# ledHeart.net
KiCad netlist of a schematic drawn in EAGLE
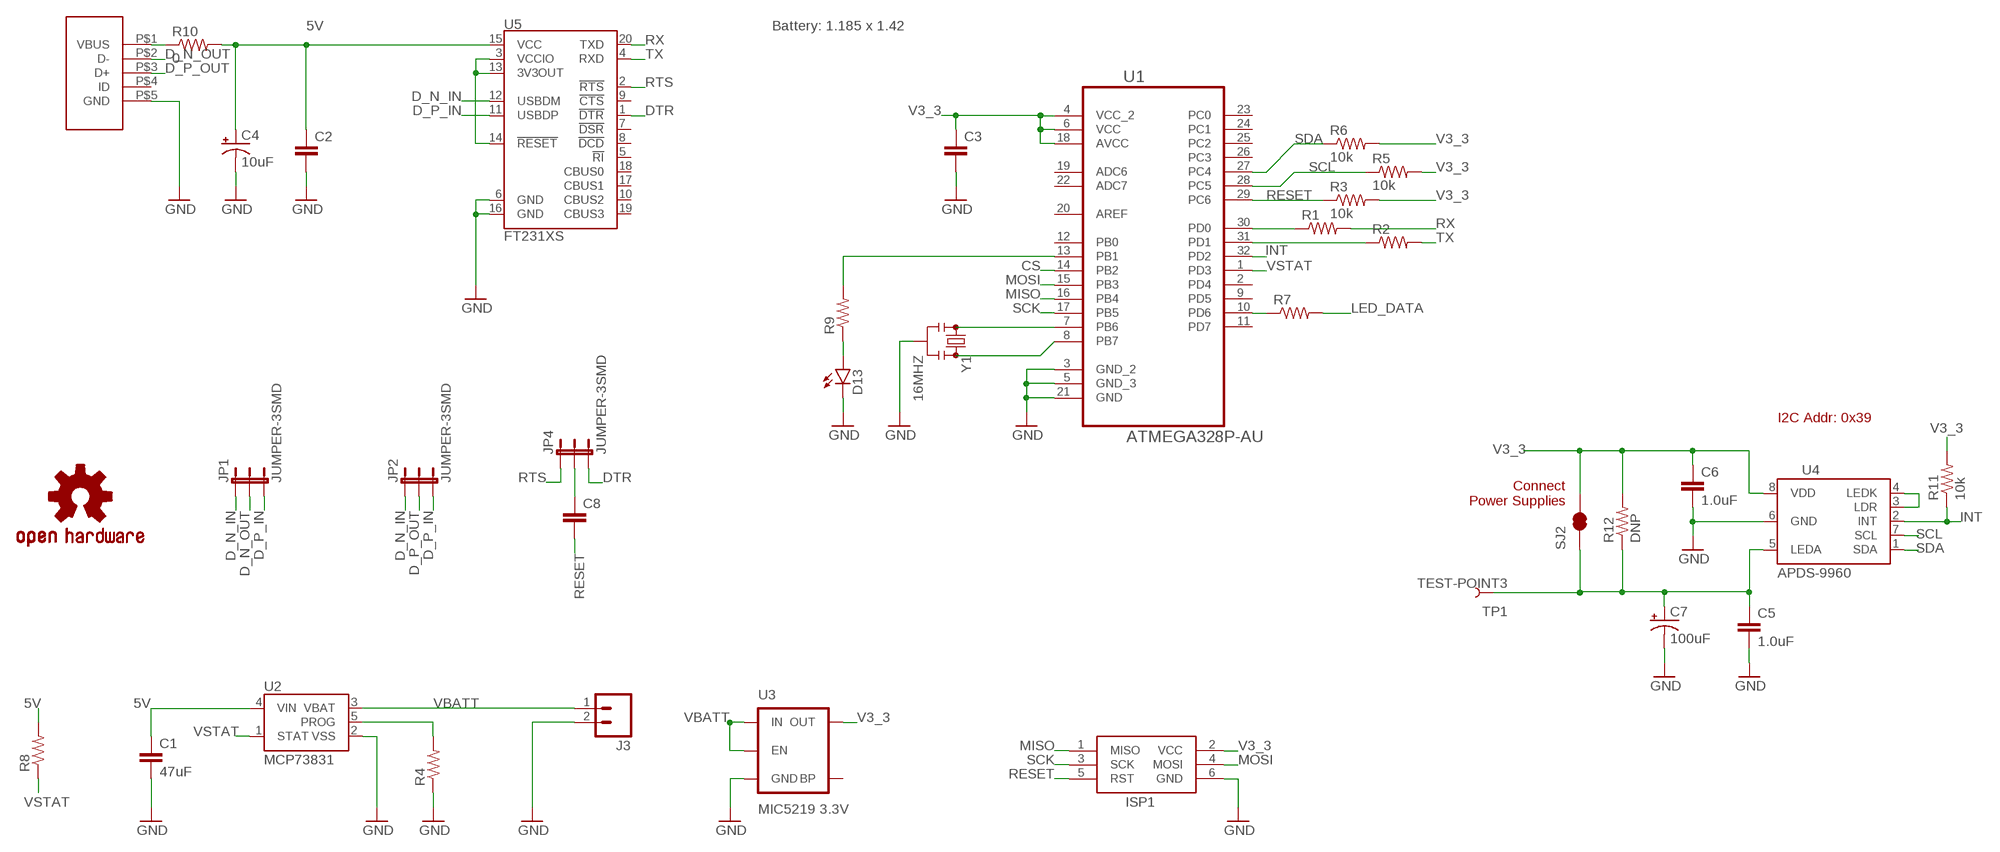
[diagram p0: schematic, sheet 1]

(export (version "E")
  (design (tool "Eeschema 10.0.6"))
  (components
    (comp (ref "C1")
      (value "47uF")
      (footprint "eagle-import:0603-CAP@1")
      (libsource (lib "eagle-import") (part "CAP0603-CAP"))
    )
    (comp (ref "C2")
      (value "CAP0603-CAP")
      (footprint "eagle-import:0603-CAP@1")
      (libsource (lib "eagle-import") (part "CAP0603-CAP"))
    )
    (comp (ref "C3")
      (value "CAP0603-CAP")
      (footprint "eagle-import:0603-CAP@1")
      (libsource (lib "eagle-import") (part "CAP0603-CAP"))
    )
    (comp (ref "C4")
      (value "10uF")
      (footprint "eagle-import:0603-POL")
      (libsource (lib "eagle-import") (part "10UF-6.3V-20%(0603)(TANT){dblquote}"))
    )
    (comp (ref "C5")
      (value "1.0uF")
      (footprint "eagle-import:0603-CAP")
      (libsource (lib "eagle-import") (part "1.0UF-16V-10%(0603)"))
    )
    (comp (ref "C6")
      (value "1.0uF")
      (footprint "eagle-import:0603-CAP")
      (libsource (lib "eagle-import") (part "1.0UF-16V-10%(0603)"))
    )
    (comp (ref "C7")
      (value "100uF")
      (footprint "eagle-import:EIA7343")
      (libsource (lib "eagle-import") (part "100UF-10V-10%(TANT)"))
    )
    (comp (ref "C8")
      (value "CAP0603-CAP")
      (footprint "eagle-import:0603-CAP@1")
      (libsource (lib "eagle-import") (part "CAP0603-CAP"))
    )
    (comp (ref "D13")
      (value "LED0603")
      (footprint "eagle-import:LED-0603")
      (libsource (lib "eagle-import") (part "LED0603"))
    )
    (comp (ref "ISP1")
      (value "AVRISP-BOX")
      (footprint "eagle-import:AVRISP-BOX")
      (libsource (lib "eagle-import") (part "AVRISP-BOX"))
    )
    (comp (ref "J3")
      (value "M02PTH")
      (footprint "eagle-import:1X02")
      (libsource (lib "eagle-import") (part "M02PTH"))
    )
    (comp (ref "JP1")
      (value "JUMPER-3SMD")
      (footprint "eagle-import:SJ_3")
      (libsource (lib "eagle-import") (part "JUMPER-3SMD"))
    )
    (comp (ref "JP2")
      (value "JUMPER-3SMD")
      (footprint "eagle-import:SJ_3")
      (libsource (lib "eagle-import") (part "JUMPER-3SMD"))
    )
    (comp (ref "JP4")
      (value "JUMPER-3SMD")
      (footprint "eagle-import:SJ_3")
      (libsource (lib "eagle-import") (part "JUMPER-3SMD"))
    )
    (comp (ref "LOGO1")
      (value "OSHW-LOGOMINI")
      (footprint "eagle-import:OSHW-LOGO-MINI")
      (libsource (lib "eagle-import") (part "OSHW-LOGOMINI"))
    )
    (comp (ref "R1")
      (value "RESISTOR0603-RES")
      (footprint "eagle-import:0603-RES")
      (libsource (lib "eagle-import") (part "RESISTOR0603-RES"))
    )
    (comp (ref "R2")
      (value "RESISTOR0603-RES")
      (footprint "eagle-import:0603-RES")
      (libsource (lib "eagle-import") (part "RESISTOR0603-RES"))
    )
    (comp (ref "R3")
      (value "10k")
      (footprint "eagle-import:0603-RES")
      (libsource (lib "eagle-import") (part "RESISTOR0603-RES"))
    )
    (comp (ref "R4")
      (value "RESISTOR0603-RES")
      (footprint "eagle-import:0603-RES")
      (libsource (lib "eagle-import") (part "RESISTOR0603-RES"))
    )
    (comp (ref "R5")
      (value "10k")
      (footprint "eagle-import:0603-RES")
      (libsource (lib "eagle-import") (part "RESISTOR0603-RES"))
    )
    (comp (ref "R6")
      (value "10k")
      (footprint "eagle-import:0603-RES")
      (libsource (lib "eagle-import") (part "RESISTOR0603-RES"))
    )
    (comp (ref "R7")
      (value "RESISTOR0603-RES")
      (footprint "eagle-import:0603-RES")
      (libsource (lib "eagle-import") (part "RESISTOR0603-RES"))
    )
    (comp (ref "R8")
      (value "RESISTOR0603-RES")
      (footprint "eagle-import:0603-RES")
      (libsource (lib "eagle-import") (part "RESISTOR0603-RES"))
    )
    (comp (ref "R9")
      (value "RESISTOR0603-RES")
      (footprint "eagle-import:0603-RES")
      (libsource (lib "eagle-import") (part "RESISTOR0603-RES"))
    )
    (comp (ref "R10")
      (value "0")
      (footprint "eagle-import:0603-RES")
      (libsource (lib "eagle-import") (part "RESISTOR0603-RES"))
    )
    (comp (ref "R11")
      (value "10k")
      (footprint "eagle-import:0603-RES")
      (libsource (lib "eagle-import") (part "10KOHM1/10W1%(0603)0603"))
    )
    (comp (ref "R12")
      (value "DNP")
      (footprint "eagle-import:0603-RES")
      (libsource (lib "eagle-import") (part "RESISTOR0603"))
    )
    (comp (ref "SJ2")
      (value "SOLDERJUMPERNC")
      (footprint "eagle-import:SJ_2S")
      (libsource (lib "eagle-import") (part "SOLDERJUMPERNC"))
    )
    (comp (ref "TP1")
      (value "TEST-POINT3")
      (footprint "eagle-import:PAD.03X.03")
      (libsource (lib "eagle-import") (part "TEST-POINT3"))
    )
    (comp (ref "U$2")
      (value "TE_USB_A121025CT")
      (footprint "eagle-import:TE_USB_A121025CT")
      (libsource (lib "eagle-import") (part "TE_USB_A121025CT"))
    )
    (comp (ref "U1")
      (value "ATMEGA328P-AU")
      (footprint "eagle-import:QFP80P900X900X120-32N")
      (libsource (lib "eagle-import") (part "ATMEGA328P-AU"))
    )
    (comp (ref "U2")
      (value "MCP73831")
      (footprint "eagle-import:SOT23-5")
      (libsource (lib "eagle-import") (part "MCP73831"))
    )
    (comp (ref "U3")
      (value "MIC5219 3.3V")
      (footprint "eagle-import:SOT23-5")
      (libsource (lib "eagle-import") (part "V_REG_MIC52193.3V"))
    )
    (comp (ref "U4")
      (value "APDS-9960")
      (footprint "eagle-import:APDS-9960")
      (libsource (lib "eagle-import") (part "APDS-9960"))
    )
    (comp (ref "U5")
      (value "FT231XS")
      (footprint "eagle-import:SSOP20_L")
      (libsource (lib "eagle-import") (part "FT231XS"))
    )
    (comp (ref "Y1")
      (value "16MHZ")
      (footprint "eagle-import:RESONATOR-SMD")
      (libsource (lib "eagle-import") (part "RESONATOR16MHZ"))
    )
  )
  (nets
    (net (code "1") (name "/5V") (class "Default")
      (node (ref "C1") (pin "1") (pinfunction "1_1") (pintype "passive"))
      (node (ref "C2") (pin "1") (pinfunction "1_1") (pintype "passive"))
      (node (ref "C4") (pin "A") (pinfunction "+_A") (pintype "passive"))
      (node (ref "R10") (pin "2") (pinfunction "2_2") (pintype "passive"))
      (node (ref "R8") (pin "2") (pinfunction "2_2") (pintype "passive"))
      (node (ref "U2") (pin "4") (pinfunction "VIN_4") (pintype "power_in"))
      (node (ref "U5") (pin "15") (pinfunction "VCC_15") (pintype "bidirectional"))
    )
    (net (code "2") (name "/CS") (class "Default")
      (node (ref "U1") (pin "14") (pinfunction "PB2_14") (pintype "bidirectional"))
    )
    (net (code "3") (name "/DTR") (class "Default")
      (node (ref "JP4") (pin "3") (pinfunction "3_3") (pintype "passive"))
      (node (ref "U5") (pin "1") (pinfunction "~{DTR}_1") (pintype "bidirectional"))
    )
    (net (code "4") (name "/D_N_IN") (class "Default")
      (node (ref "JP1") (pin "1") (pinfunction "1_1") (pintype "passive"))
      (node (ref "JP2") (pin "1") (pinfunction "1_1") (pintype "passive"))
      (node (ref "U5") (pin "12") (pinfunction "USBDM_12") (pintype "bidirectional"))
    )
    (net (code "5") (name "/D_N_OUT") (class "Default")
      (node (ref "JP1") (pin "2") (pinfunction "2_2") (pintype "passive"))
      (node (ref "U$2") (pin "P$2") (pinfunction "D-_P$2") (pintype "bidirectional"))
    )
    (net (code "6") (name "/D_P_IN") (class "Default")
      (node (ref "JP1") (pin "3") (pinfunction "3_3") (pintype "passive"))
      (node (ref "JP2") (pin "3") (pinfunction "3_3") (pintype "passive"))
      (node (ref "U5") (pin "11") (pinfunction "USBDP_11") (pintype "bidirectional"))
    )
    (net (code "7") (name "/D_P_OUT") (class "Default")
      (node (ref "JP2") (pin "2") (pinfunction "2_2") (pintype "passive"))
      (node (ref "U$2") (pin "P$3") (pinfunction "D+_P$3") (pintype "bidirectional"))
    )
    (net (code "8") (name "/INT") (class "Default")
      (node (ref "R11") (pin "1") (pinfunction "1_1") (pintype "passive"))
      (node (ref "U1") (pin "32") (pinfunction "PD2_32") (pintype "bidirectional"))
      (node (ref "U4") (pin "2") (pinfunction "INT_2") (pintype "bidirectional"))
    )
    (net (code "9") (name "/LED_DATA") (class "Default")
      (node (ref "R7") (pin "2") (pinfunction "2_2") (pintype "passive"))
    )
    (net (code "10") (name "/MISO") (class "Default")
      (node (ref "ISP1") (pin "1") (pinfunction "MISO_1") (pintype "input"))
      (node (ref "U1") (pin "16") (pinfunction "PB4_16") (pintype "bidirectional"))
    )
    (net (code "11") (name "/MOSI") (class "Default")
      (node (ref "ISP1") (pin "4") (pinfunction "MOSI_4") (pintype "output"))
      (node (ref "U1") (pin "15") (pinfunction "PB3_15") (pintype "bidirectional"))
    )
    (net (code "12") (name "/RESET") (class "Default")
      (node (ref "C8") (pin "2") (pinfunction "2_2") (pintype "passive"))
      (node (ref "ISP1") (pin "5") (pinfunction "RST_5") (pintype "output"))
      (node (ref "R3") (pin "1") (pinfunction "1_1") (pintype "passive"))
      (node (ref "U1") (pin "29") (pinfunction "PC6_29") (pintype "bidirectional"))
    )
    (net (code "13") (name "/RTS") (class "Default")
      (node (ref "JP4") (pin "1") (pinfunction "1_1") (pintype "passive"))
      (node (ref "U5") (pin "2") (pinfunction "~{RTS}_2") (pintype "bidirectional"))
    )
    (net (code "14") (name "/RX") (class "Default")
      (node (ref "R1") (pin "2") (pinfunction "2_2") (pintype "passive"))
      (node (ref "U5") (pin "20") (pinfunction "TXD_20") (pintype "bidirectional"))
    )
    (net (code "15") (name "/SCK") (class "Default")
      (node (ref "ISP1") (pin "3") (pinfunction "SCK_3") (pintype "output"))
      (node (ref "U1") (pin "17") (pinfunction "PB5_17") (pintype "bidirectional"))
    )
    (net (code "16") (name "/SCL") (class "Default")
      (node (ref "R5") (pin "1") (pinfunction "1_1") (pintype "passive"))
      (node (ref "U1") (pin "28") (pinfunction "PC5_28") (pintype "bidirectional"))
      (node (ref "U4") (pin "7") (pinfunction "SCL_7") (pintype "bidirectional"))
    )
    (net (code "17") (name "/SDA") (class "Default")
      (node (ref "R6") (pin "1") (pinfunction "1_1") (pintype "passive"))
      (node (ref "U1") (pin "27") (pinfunction "PC4_27") (pintype "bidirectional"))
      (node (ref "U4") (pin "1") (pinfunction "SDA_1") (pintype "bidirectional"))
    )
    (net (code "18") (name "/TX") (class "Default")
      (node (ref "R2") (pin "2") (pinfunction "2_2") (pintype "passive"))
      (node (ref "U5") (pin "4") (pinfunction "RXD_4") (pintype "bidirectional"))
    )
    (net (code "19") (name "/V3_3") (class "Default")
      (node (ref "C3") (pin "1") (pinfunction "1_1") (pintype "passive"))
      (node (ref "C6") (pin "1") (pinfunction "1_1") (pintype "passive"))
      (node (ref "ISP1") (pin "2") (pinfunction "VCC_2") (pintype "power_in"))
      (node (ref "R11") (pin "2") (pinfunction "2_2") (pintype "passive"))
      (node (ref "R12") (pin "2") (pinfunction "2_2") (pintype "passive"))
      (node (ref "R3") (pin "2") (pinfunction "2_2") (pintype "passive"))
      (node (ref "R5") (pin "2") (pinfunction "2_2") (pintype "passive"))
      (node (ref "R6") (pin "2") (pinfunction "2_2") (pintype "passive"))
      (node (ref "SJ2") (pin "2") (pinfunction "2_2") (pintype "passive"))
      (node (ref "U1") (pin "18") (pinfunction "AVCC_18") (pintype "power_in"))
      (node (ref "U1") (pin "4") (pinfunction "VCC_2_4") (pintype "power_in"))
      (node (ref "U1") (pin "6") (pinfunction "VCC_6") (pintype "power_in"))
      (node (ref "U3") (pin "5") (pinfunction "OUT_5") (pintype "passive"))
      (node (ref "U4") (pin "8") (pinfunction "VDD_8") (pintype "bidirectional"))
    )
    (net (code "20") (name "/VBATT") (class "Default")
      (node (ref "J3") (pin "1") (pinfunction "1_1") (pintype "passive"))
      (node (ref "U2") (pin "3") (pinfunction "VBAT_3") (pintype "power_in"))
      (node (ref "U3") (pin "1") (pinfunction "IN_1") (pintype "input"))
      (node (ref "U3") (pin "3") (pinfunction "EN_3") (pintype "input"))
    )
    (net (code "21") (name "/VSTAT") (class "Default")
      (node (ref "R8") (pin "1") (pinfunction "1_1") (pintype "passive"))
      (node (ref "U1") (pin "1") (pinfunction "PD3_1") (pintype "bidirectional"))
      (node (ref "U2") (pin "1") (pinfunction "STAT_1") (pintype "output"))
    )
    (net (code "22") (name "GND") (class "Default")
      (node (ref "C1") (pin "2") (pinfunction "2_2") (pintype "passive"))
      (node (ref "C2") (pin "2") (pinfunction "2_2") (pintype "passive"))
      (node (ref "C3") (pin "2") (pinfunction "2_2") (pintype "passive"))
      (node (ref "C4") (pin "K") (pinfunction "-_K") (pintype "passive"))
      (node (ref "C5") (pin "2") (pinfunction "2_2") (pintype "passive"))
      (node (ref "C6") (pin "2") (pinfunction "2_2") (pintype "passive"))
      (node (ref "C7") (pin "C") (pinfunction "-_C") (pintype "passive"))
      (node (ref "D13") (pin "C") (pinfunction "C_C") (pintype "passive"))
      (node (ref "ISP1") (pin "6") (pinfunction "GND_6") (pintype "power_in"))
      (node (ref "J3") (pin "2") (pinfunction "2_2") (pintype "passive"))
      (node (ref "R4") (pin "1") (pinfunction "1_1") (pintype "passive"))
      (node (ref "U$2") (pin "P$5") (pinfunction "GND_P$5") (pintype "bidirectional"))
      (node (ref "U1") (pin "21") (pinfunction "GND_21") (pintype "passive"))
      (node (ref "U1") (pin "3") (pinfunction "GND_2_3") (pintype "passive"))
      (node (ref "U1") (pin "5") (pinfunction "GND_3_5") (pintype "passive"))
      (node (ref "U2") (pin "2") (pinfunction "VSS_2") (pintype "power_in"))
      (node (ref "U3") (pin "2") (pinfunction "GND_2") (pintype "input"))
      (node (ref "U4") (pin "6") (pinfunction "GND_6") (pintype "bidirectional"))
      (node (ref "U5") (pin "16") (pinfunction "GND_16") (pintype "bidirectional"))
      (node (ref "U5") (pin "6") (pinfunction "GND_6") (pintype "bidirectional"))
      (node (ref "Y1") (pin "2") (pinfunction "2_2") (pintype "passive"))
    )
    (net (code "23") (name "Net-(C7-+)") (class "Default")
      (node (ref "C5") (pin "1") (pinfunction "1_1") (pintype "passive"))
      (node (ref "C7") (pin "A") (pinfunction "+_A") (pintype "passive"))
      (node (ref "R12") (pin "1") (pinfunction "1_1") (pintype "passive"))
      (node (ref "SJ2") (pin "1") (pinfunction "1_1") (pintype "passive"))
      (node (ref "U4") (pin "5") (pinfunction "LEDA_5") (pintype "bidirectional"))
    )
    (net (code "24") (name "Net-(C8-Pad1)") (class "Default")
      (node (ref "C8") (pin "1") (pinfunction "1_1") (pintype "passive"))
      (node (ref "JP4") (pin "2") (pinfunction "2_2") (pintype "passive"))
    )
    (net (code "25") (name "Net-(D13-PadA)") (class "Default")
      (node (ref "D13") (pin "A") (pinfunction "A_A") (pintype "passive"))
      (node (ref "R9") (pin "1") (pinfunction "1_1") (pintype "passive"))
    )
    (net (code "26") (name "Net-(U$2-VBUS)") (class "Default")
      (node (ref "R10") (pin "1") (pinfunction "1_1") (pintype "passive"))
      (node (ref "U$2") (pin "P$1") (pinfunction "VBUS_P$1") (pintype "bidirectional"))
    )
    (net (code "27") (name "Net-(U1-PB1)") (class "Default")
      (node (ref "R9") (pin "2") (pinfunction "2_2") (pintype "passive"))
      (node (ref "U1") (pin "13") (pinfunction "PB1_13") (pintype "bidirectional"))
    )
    (net (code "28") (name "Net-(U1-PB6)") (class "Default")
      (node (ref "U1") (pin "7") (pinfunction "PB6_7") (pintype "bidirectional"))
      (node (ref "Y1") (pin "1") (pinfunction "1_1") (pintype "passive"))
    )
    (net (code "29") (name "Net-(U1-PB7)") (class "Default")
      (node (ref "U1") (pin "8") (pinfunction "PB7_8") (pintype "bidirectional"))
      (node (ref "Y1") (pin "3") (pinfunction "3_3") (pintype "passive"))
    )
    (net (code "30") (name "Net-(U1-PD0)") (class "Default")
      (node (ref "R1") (pin "1") (pinfunction "1_1") (pintype "passive"))
      (node (ref "U1") (pin "30") (pinfunction "PD0_30") (pintype "bidirectional"))
    )
    (net (code "31") (name "Net-(U1-PD1)") (class "Default")
      (node (ref "R2") (pin "1") (pinfunction "1_1") (pintype "passive"))
      (node (ref "U1") (pin "31") (pinfunction "PD1_31") (pintype "bidirectional"))
    )
    (net (code "32") (name "Net-(U1-PD6)") (class "Default")
      (node (ref "R7") (pin "1") (pinfunction "1_1") (pintype "passive"))
      (node (ref "U1") (pin "10") (pinfunction "PD6_10") (pintype "bidirectional"))
    )
    (net (code "33") (name "Net-(U2-PROG)") (class "Default")
      (node (ref "R4") (pin "2") (pinfunction "2_2") (pintype "passive"))
      (node (ref "U2") (pin "5") (pinfunction "PROG_5") (pintype "input"))
    )
    (net (code "34") (name "Net-(U4-LDR)") (class "Default")
      (node (ref "U4") (pin "3") (pinfunction "LDR_3") (pintype "bidirectional"))
      (node (ref "U4") (pin "4") (pinfunction "LEDK_4") (pintype "bidirectional"))
    )
    (net (code "35") (name "Net-(U5-3V3OUT)") (class "Default")
      (node (ref "U5") (pin "13") (pinfunction "3V3OUT_13") (pintype "bidirectional"))
      (node (ref "U5") (pin "14") (pinfunction "~{RESET}_14") (pintype "bidirectional"))
      (node (ref "U5") (pin "3") (pinfunction "VCCIO_3") (pintype "bidirectional"))
    )
    (net (code "36") (name "unconnected-(TP1-1-PadP$1)") (class "Default")
      (node (ref "TP1") (pin "P$1") (pinfunction "1_P$1") (pintype "bidirectional"))
    )
    (net (code "37") (name "unconnected-(U$2-ID-PadP$4)") (class "Default")
      (node (ref "U$2") (pin "P$4") (pinfunction "ID_P$4") (pintype "bidirectional"))
    )
    (net (code "38") (name "unconnected-(U1-ADC6-Pad19)") (class "Default")
      (node (ref "U1") (pin "19") (pinfunction "ADC6_19") (pintype "input"))
    )
    (net (code "39") (name "unconnected-(U1-ADC7-Pad22)") (class "Default")
      (node (ref "U1") (pin "22") (pinfunction "ADC7_22") (pintype "input"))
    )
    (net (code "40") (name "unconnected-(U1-AREF-Pad20)") (class "Default")
      (node (ref "U1") (pin "20") (pinfunction "AREF_20") (pintype "input"))
    )
    (net (code "41") (name "unconnected-(U1-PB0-Pad12)") (class "Default")
      (node (ref "U1") (pin "12") (pinfunction "PB0_12") (pintype "bidirectional"))
    )
    (net (code "42") (name "unconnected-(U1-PC0-Pad23)") (class "Default")
      (node (ref "U1") (pin "23") (pinfunction "PC0_23") (pintype "bidirectional"))
    )
    (net (code "43") (name "unconnected-(U1-PC1-Pad24)") (class "Default")
      (node (ref "U1") (pin "24") (pinfunction "PC1_24") (pintype "bidirectional"))
    )
    (net (code "44") (name "unconnected-(U1-PC2-Pad25)") (class "Default")
      (node (ref "U1") (pin "25") (pinfunction "PC2_25") (pintype "bidirectional"))
    )
    (net (code "45") (name "unconnected-(U1-PC3-Pad26)") (class "Default")
      (node (ref "U1") (pin "26") (pinfunction "PC3_26") (pintype "bidirectional"))
    )
    (net (code "46") (name "unconnected-(U1-PD4-Pad2)") (class "Default")
      (node (ref "U1") (pin "2") (pinfunction "PD4_2") (pintype "bidirectional"))
    )
    (net (code "47") (name "unconnected-(U1-PD5-Pad9)") (class "Default")
      (node (ref "U1") (pin "9") (pinfunction "PD5_9") (pintype "bidirectional"))
    )
    (net (code "48") (name "unconnected-(U1-PD7-Pad11)") (class "Default")
      (node (ref "U1") (pin "11") (pinfunction "PD7_11") (pintype "bidirectional"))
    )
    (net (code "49") (name "unconnected-(U3-BP-Pad4)") (class "Default")
      (node (ref "U3") (pin "4") (pinfunction "BP_4") (pintype "input"))
    )
    (net (code "50") (name "unconnected-(U5-CBUS0-Pad18)") (class "Default")
      (node (ref "U5") (pin "18") (pinfunction "CBUS0_18") (pintype "bidirectional"))
    )
    (net (code "51") (name "unconnected-(U5-CBUS1-Pad17)") (class "Default")
      (node (ref "U5") (pin "17") (pinfunction "CBUS1_17") (pintype "bidirectional"))
    )
    (net (code "52") (name "unconnected-(U5-CBUS2-Pad10)") (class "Default")
      (node (ref "U5") (pin "10") (pinfunction "CBUS2_10") (pintype "bidirectional"))
    )
    (net (code "53") (name "unconnected-(U5-CBUS3-Pad19)") (class "Default")
      (node (ref "U5") (pin "19") (pinfunction "CBUS3_19") (pintype "bidirectional"))
    )
    (net (code "54") (name "unconnected-(U5-~{CTS}-Pad9)") (class "Default")
      (node (ref "U5") (pin "9") (pinfunction "~{CTS}_9") (pintype "bidirectional"))
    )
    (net (code "55") (name "unconnected-(U5-~{DCD}-Pad8)") (class "Default")
      (node (ref "U5") (pin "8") (pinfunction "~{DCD}_8") (pintype "bidirectional"))
    )
    (net (code "56") (name "unconnected-(U5-~{DSR}-Pad7)") (class "Default")
      (node (ref "U5") (pin "7") (pinfunction "~{DSR}_7") (pintype "bidirectional"))
    )
    (net (code "57") (name "unconnected-(U5-~{RI}-Pad5)") (class "Default")
      (node (ref "U5") (pin "5") (pinfunction "~{RI}_5") (pintype "bidirectional"))
    )
  )
)
